# pc386ram-nobuf.net
KiCad netlist of a schematic drawn in EAGLE
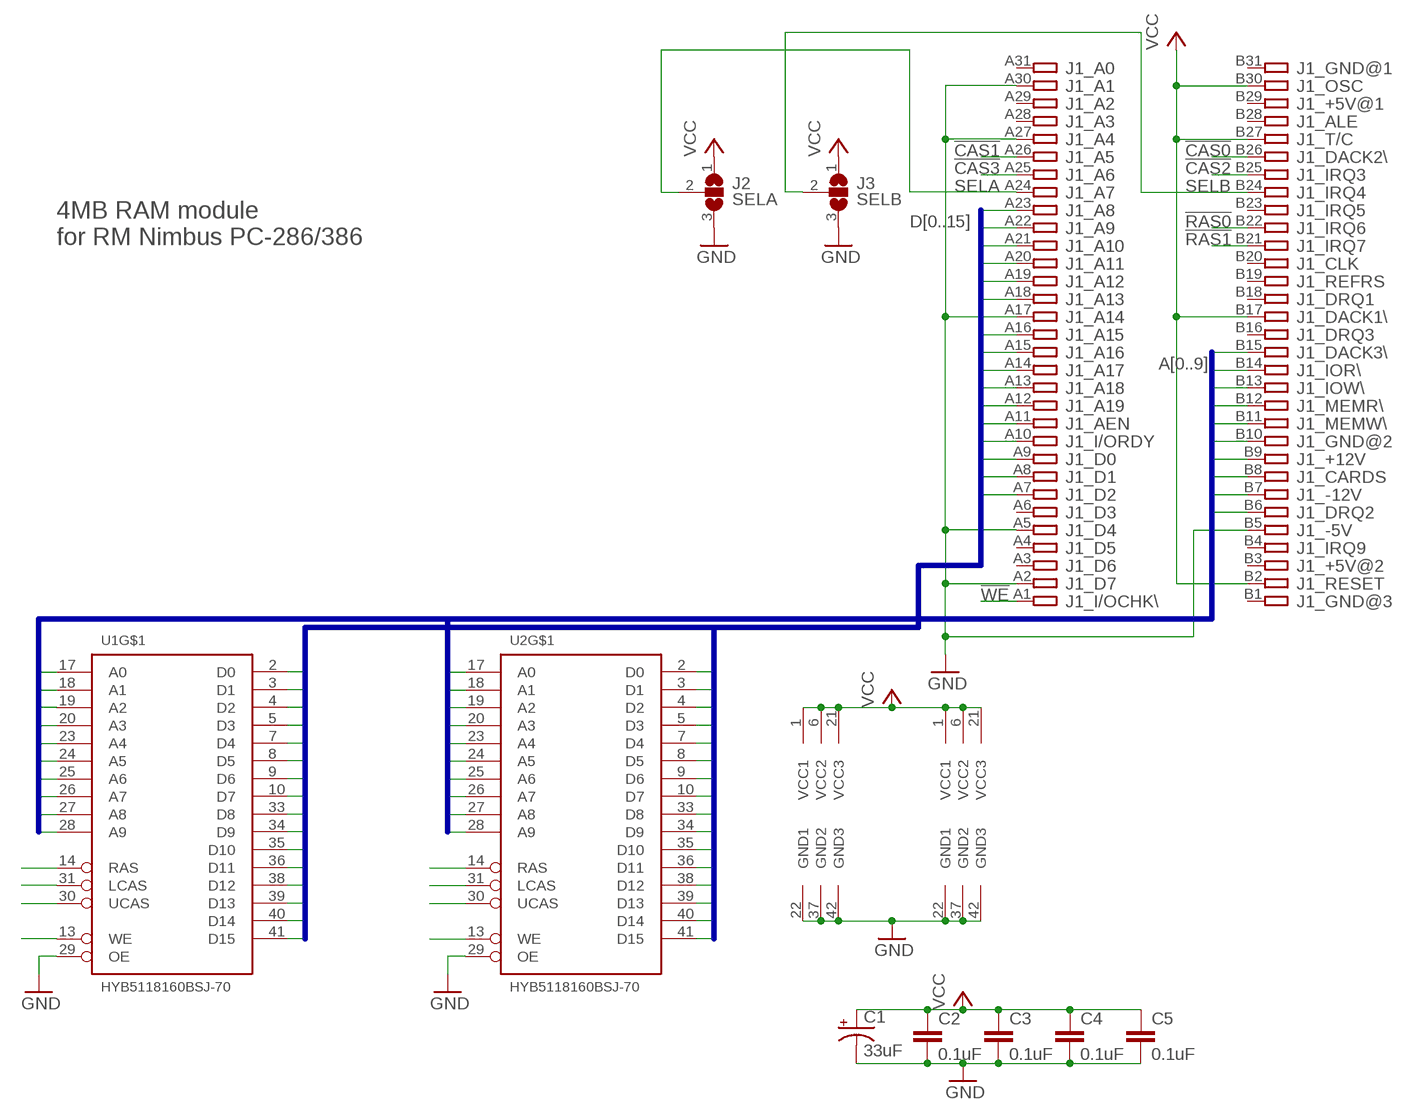
[diagram p0: schematic, sheet 1]

(export (version "E")
  (design (tool "Eeschema 10.0.6"))
  (components
    (comp (ref "C1")
      (value "33uF")
      (footprint "eagle-import:E2,5-7")
      (libsource (lib "eagle-import") (part "CPOL-USE2.5-7"))
    )
    (comp (ref "C2")
      (value "0.1uF")
      (footprint "eagle-import:C050-024X044")
      (libsource (lib "eagle-import") (part "C-EU050-024X044"))
    )
    (comp (ref "C3")
      (value "0.1uF")
      (footprint "eagle-import:C050-024X044")
      (libsource (lib "eagle-import") (part "C-EU050-024X044"))
    )
    (comp (ref "C4")
      (value "0.1uF")
      (footprint "eagle-import:C050-024X044")
      (libsource (lib "eagle-import") (part "C-EU050-024X044"))
    )
    (comp (ref "C5")
      (value "0.1uF")
      (footprint "eagle-import:C050-024X044")
      (libsource (lib "eagle-import") (part "C-EU050-024X044"))
    )
    (comp (ref "J1")
      (value "PC-386 RAM slot")
      (footprint "eagle-import:IBM8BIT")
      (libsource (lib "eagle-import") (part "IBM8BIT"))
    )
    (comp (ref "J2")
      (value "SELA")
      (footprint "eagle-import:SJ_2")
      (libsource (lib "eagle-import") (part "SJ2W"))
    )
    (comp (ref "J3")
      (value "SELB")
      (footprint "eagle-import:SJ_2")
      (libsource (lib "eagle-import") (part "SJ2W"))
    )
    (comp (ref "U1")
      (value "HYB5118160BSJ-70")
      (footprint "eagle-import:SOJ-42")
      (libsource (lib "eagle-import") (part "HYB5118160BSJ-70"))
    )
    (comp (ref "U2")
      (value "HYB5118160BSJ-70")
      (footprint "eagle-import:SOJ-42")
      (libsource (lib "eagle-import") (part "HYB5118160BSJ-70"))
    )
  )
  (nets
    (net (code "1") (name "/A0") (class "Default")
      (node (ref "J1") (pin "B6") (pinfunction "P_B6") (pintype "bidirectional"))
      (node (ref "U1") (pin "17") (pinfunction "A0_17") (pintype "input"))
      (node (ref "U2") (pin "17") (pinfunction "A0_17") (pintype "input"))
    )
    (net (code "2") (name "/A1") (class "Default")
      (node (ref "J1") (pin "B7") (pinfunction "P_B7") (pintype "bidirectional"))
      (node (ref "U1") (pin "18") (pinfunction "A1_18") (pintype "input"))
      (node (ref "U2") (pin "18") (pinfunction "A1_18") (pintype "input"))
    )
    (net (code "3") (name "/A2") (class "Default")
      (node (ref "J1") (pin "B8") (pinfunction "P_B8") (pintype "bidirectional"))
      (node (ref "U1") (pin "19") (pinfunction "A2_19") (pintype "input"))
      (node (ref "U2") (pin "19") (pinfunction "A2_19") (pintype "input"))
    )
    (net (code "4") (name "/A3") (class "Default")
      (node (ref "J1") (pin "B9") (pinfunction "P_B9") (pintype "bidirectional"))
      (node (ref "U1") (pin "20") (pinfunction "A3_20") (pintype "input"))
      (node (ref "U2") (pin "20") (pinfunction "A3_20") (pintype "input"))
    )
    (net (code "5") (name "/A4") (class "Default")
      (node (ref "J1") (pin "B10") (pinfunction "P_B10") (pintype "bidirectional"))
      (node (ref "U1") (pin "23") (pinfunction "A4_23") (pintype "input"))
      (node (ref "U2") (pin "23") (pinfunction "A4_23") (pintype "input"))
    )
    (net (code "6") (name "/A5") (class "Default")
      (node (ref "J1") (pin "B11") (pinfunction "P_B11") (pintype "bidirectional"))
      (node (ref "U1") (pin "24") (pinfunction "A5_24") (pintype "input"))
      (node (ref "U2") (pin "24") (pinfunction "A5_24") (pintype "input"))
    )
    (net (code "7") (name "/A6") (class "Default")
      (node (ref "J1") (pin "B12") (pinfunction "P_B12") (pintype "bidirectional"))
      (node (ref "U1") (pin "25") (pinfunction "A6_25") (pintype "input"))
      (node (ref "U2") (pin "25") (pinfunction "A6_25") (pintype "input"))
    )
    (net (code "8") (name "/A7") (class "Default")
      (node (ref "J1") (pin "B13") (pinfunction "P_B13") (pintype "bidirectional"))
      (node (ref "U1") (pin "26") (pinfunction "A7_26") (pintype "input"))
      (node (ref "U2") (pin "26") (pinfunction "A7_26") (pintype "input"))
    )
    (net (code "9") (name "/A8") (class "Default")
      (node (ref "J1") (pin "B14") (pinfunction "P_B14") (pintype "bidirectional"))
      (node (ref "U1") (pin "27") (pinfunction "A8_27") (pintype "input"))
      (node (ref "U2") (pin "27") (pinfunction "A8_27") (pintype "input"))
    )
    (net (code "10") (name "/A9") (class "Default")
      (node (ref "J1") (pin "B15") (pinfunction "P_B15") (pintype "bidirectional"))
      (node (ref "U1") (pin "28") (pinfunction "A9_28") (pintype "input"))
      (node (ref "U2") (pin "28") (pinfunction "A9_28") (pintype "input"))
    )
    (net (code "12") (name "/D0") (class "Default")
      (node (ref "J1") (pin "A7") (pinfunction "P_A7") (pintype "bidirectional"))
      (node (ref "U1") (pin "2") (pinfunction "D0_2") (pintype "bidirectional"))
      (node (ref "U2") (pin "2") (pinfunction "D0_2") (pintype "bidirectional"))
    )
    (net (code "13") (name "/D1") (class "Default")
      (node (ref "J1") (pin "A8") (pinfunction "P_A8") (pintype "bidirectional"))
      (node (ref "U1") (pin "3") (pinfunction "D1_3") (pintype "bidirectional"))
      (node (ref "U2") (pin "3") (pinfunction "D1_3") (pintype "bidirectional"))
    )
    (net (code "14") (name "/D2") (class "Default")
      (node (ref "J1") (pin "A9") (pinfunction "P_A9") (pintype "bidirectional"))
      (node (ref "U1") (pin "4") (pinfunction "D2_4") (pintype "bidirectional"))
      (node (ref "U2") (pin "4") (pinfunction "D2_4") (pintype "bidirectional"))
    )
    (net (code "15") (name "/D3") (class "Default")
      (node (ref "J1") (pin "A10") (pinfunction "P_A10") (pintype "bidirectional"))
      (node (ref "U1") (pin "5") (pinfunction "D3_5") (pintype "bidirectional"))
      (node (ref "U2") (pin "5") (pinfunction "D3_5") (pintype "bidirectional"))
    )
    (net (code "16") (name "/D4") (class "Default")
      (node (ref "J1") (pin "A11") (pinfunction "P_A11") (pintype "bidirectional"))
      (node (ref "U1") (pin "7") (pinfunction "D4_7") (pintype "bidirectional"))
      (node (ref "U2") (pin "7") (pinfunction "D4_7") (pintype "bidirectional"))
    )
    (net (code "17") (name "/D5") (class "Default")
      (node (ref "J1") (pin "A12") (pinfunction "P_A12") (pintype "bidirectional"))
      (node (ref "U1") (pin "8") (pinfunction "D5_8") (pintype "bidirectional"))
      (node (ref "U2") (pin "8") (pinfunction "D5_8") (pintype "bidirectional"))
    )
    (net (code "18") (name "/D6") (class "Default")
      (node (ref "J1") (pin "A13") (pinfunction "P_A13") (pintype "bidirectional"))
      (node (ref "U1") (pin "9") (pinfunction "D6_9") (pintype "bidirectional"))
      (node (ref "U2") (pin "9") (pinfunction "D6_9") (pintype "bidirectional"))
    )
    (net (code "19") (name "/D7") (class "Default")
      (node (ref "J1") (pin "A14") (pinfunction "P_A14") (pintype "bidirectional"))
      (node (ref "U1") (pin "10") (pinfunction "D7_10") (pintype "bidirectional"))
      (node (ref "U2") (pin "10") (pinfunction "D7_10") (pintype "bidirectional"))
    )
    (net (code "20") (name "/D8") (class "Default")
      (node (ref "J1") (pin "A15") (pinfunction "P_A15") (pintype "bidirectional"))
      (node (ref "U1") (pin "33") (pinfunction "D8_33") (pintype "bidirectional"))
      (node (ref "U2") (pin "33") (pinfunction "D8_33") (pintype "bidirectional"))
    )
    (net (code "21") (name "/D9") (class "Default")
      (node (ref "J1") (pin "A16") (pinfunction "P_A16") (pintype "bidirectional"))
      (node (ref "U1") (pin "34") (pinfunction "D9_34") (pintype "bidirectional"))
      (node (ref "U2") (pin "34") (pinfunction "D9_34") (pintype "bidirectional"))
    )
    (net (code "22") (name "/D10") (class "Default")
      (node (ref "J1") (pin "A18") (pinfunction "P_A18") (pintype "bidirectional"))
      (node (ref "U1") (pin "35") (pinfunction "D10_35") (pintype "bidirectional"))
      (node (ref "U2") (pin "35") (pinfunction "D10_35") (pintype "bidirectional"))
    )
    (net (code "23") (name "/D11") (class "Default")
      (node (ref "J1") (pin "A19") (pinfunction "P_A19") (pintype "bidirectional"))
      (node (ref "U1") (pin "36") (pinfunction "D11_36") (pintype "bidirectional"))
      (node (ref "U2") (pin "36") (pinfunction "D11_36") (pintype "bidirectional"))
    )
    (net (code "24") (name "/D12") (class "Default")
      (node (ref "J1") (pin "A20") (pinfunction "P_A20") (pintype "bidirectional"))
      (node (ref "U1") (pin "38") (pinfunction "D12_38") (pintype "bidirectional"))
      (node (ref "U2") (pin "38") (pinfunction "D12_38") (pintype "bidirectional"))
    )
    (net (code "25") (name "/D13") (class "Default")
      (node (ref "J1") (pin "A21") (pinfunction "P_A21") (pintype "bidirectional"))
      (node (ref "U1") (pin "39") (pinfunction "D13_39") (pintype "bidirectional"))
      (node (ref "U2") (pin "39") (pinfunction "D13_39") (pintype "bidirectional"))
    )
    (net (code "26") (name "/D14") (class "Default")
      (node (ref "J1") (pin "A22") (pinfunction "P_A22") (pintype "bidirectional"))
      (node (ref "U1") (pin "40") (pinfunction "D14_40") (pintype "bidirectional"))
      (node (ref "U2") (pin "40") (pinfunction "D14_40") (pintype "bidirectional"))
    )
    (net (code "27") (name "/D15") (class "Default")
      (node (ref "J1") (pin "A23") (pinfunction "P_A23") (pintype "bidirectional"))
      (node (ref "U1") (pin "41") (pinfunction "D15_41") (pintype "bidirectional"))
      (node (ref "U2") (pin "41") (pinfunction "D15_41") (pintype "bidirectional"))
    )
    (net (code "29") (name "/SELA") (class "Default")
      (node (ref "J1") (pin "A24") (pinfunction "P_A24") (pintype "bidirectional"))
      (node (ref "J2") (pin "2") (pinfunction "2_2") (pintype "passive"))
    )
    (net (code "30") (name "/SELB") (class "Default")
      (node (ref "J1") (pin "B24") (pinfunction "P_B24") (pintype "bidirectional"))
      (node (ref "J3") (pin "2") (pinfunction "2_2") (pintype "passive"))
    )
    (net (code "31") (name "/~{CAS0}") (class "Default")
      (node (ref "J1") (pin "B26") (pinfunction "P_B26") (pintype "bidirectional"))
      (node (ref "U1") (pin "30") (pinfunction "UCAS_30") (pintype "input"))
    )
    (net (code "32") (name "/~{CAS1}") (class "Default")
      (node (ref "J1") (pin "A26") (pinfunction "P_A26") (pintype "bidirectional"))
      (node (ref "U1") (pin "31") (pinfunction "LCAS_31") (pintype "input"))
    )
    (net (code "33") (name "/~{CAS2}") (class "Default")
      (node (ref "J1") (pin "B25") (pinfunction "P_B25") (pintype "bidirectional"))
      (node (ref "U2") (pin "30") (pinfunction "UCAS_30") (pintype "input"))
    )
    (net (code "34") (name "/~{CAS3}") (class "Default")
      (node (ref "J1") (pin "A25") (pinfunction "P_A25") (pintype "bidirectional"))
      (node (ref "U2") (pin "31") (pinfunction "LCAS_31") (pintype "input"))
    )
    (net (code "35") (name "/~{RAS0}") (class "Default")
      (node (ref "J1") (pin "B22") (pinfunction "P_B22") (pintype "bidirectional"))
      (node (ref "U1") (pin "14") (pinfunction "RAS_14") (pintype "input"))
    )
    (net (code "36") (name "/~{RAS1}") (class "Default")
      (node (ref "J1") (pin "B21") (pinfunction "P_B21") (pintype "bidirectional"))
      (node (ref "U2") (pin "14") (pinfunction "RAS_14") (pintype "input"))
    )
    (net (code "37") (name "/~{WE}") (class "Default")
      (node (ref "J1") (pin "A1") (pinfunction "P_A1") (pintype "bidirectional"))
      (node (ref "U1") (pin "13") (pinfunction "WE_13") (pintype "input"))
      (node (ref "U2") (pin "13") (pinfunction "WE_13") (pintype "input"))
    )
    (net (code "38") (name "GND") (class "Default")
      (node (ref "C1") (pin "-") (pinfunction "-_-") (pintype "passive"))
      (node (ref "C2") (pin "2") (pinfunction "2_2") (pintype "passive"))
      (node (ref "C3") (pin "2") (pinfunction "2_2") (pintype "passive"))
      (node (ref "C4") (pin "2") (pinfunction "2_2") (pintype "passive"))
      (node (ref "C5") (pin "2") (pinfunction "2_2") (pintype "passive"))
      (node (ref "J1") (pin "A17") (pinfunction "P_A17") (pintype "bidirectional"))
      (node (ref "J1") (pin "A2") (pinfunction "P_A2") (pintype "bidirectional"))
      (node (ref "J1") (pin "A27") (pinfunction "P_A27") (pintype "bidirectional"))
      (node (ref "J1") (pin "A30") (pinfunction "P_A30") (pintype "bidirectional"))
      (node (ref "J1") (pin "A5") (pinfunction "P_A5") (pintype "bidirectional"))
      (node (ref "J1") (pin "B5") (pinfunction "P_B5") (pintype "bidirectional"))
      (node (ref "J2") (pin "3") (pinfunction "3_3") (pintype "passive"))
      (node (ref "J3") (pin "3") (pinfunction "3_3") (pintype "passive"))
      (node (ref "U1") (pin "22") (pinfunction "GND1_22") (pintype "power_in"))
      (node (ref "U1") (pin "29") (pinfunction "OE_29") (pintype "input"))
      (node (ref "U1") (pin "37") (pinfunction "GND2_37") (pintype "power_in"))
      (node (ref "U1") (pin "42") (pinfunction "GND3_42") (pintype "power_in"))
      (node (ref "U2") (pin "22") (pinfunction "GND1_22") (pintype "power_in"))
      (node (ref "U2") (pin "29") (pinfunction "OE_29") (pintype "input"))
      (node (ref "U2") (pin "37") (pinfunction "GND2_37") (pintype "power_in"))
      (node (ref "U2") (pin "42") (pinfunction "GND3_42") (pintype "power_in"))
    )
    (net (code "39") (name "VCC") (class "Default")
      (node (ref "C1") (pin "+") (pinfunction "+_+") (pintype "passive"))
      (node (ref "C2") (pin "1") (pinfunction "1_1") (pintype "passive"))
      (node (ref "C3") (pin "1") (pinfunction "1_1") (pintype "passive"))
      (node (ref "C4") (pin "1") (pinfunction "1_1") (pintype "passive"))
      (node (ref "C5") (pin "1") (pinfunction "1_1") (pintype "passive"))
      (node (ref "J1") (pin "B17") (pinfunction "P_B17") (pintype "bidirectional"))
      (node (ref "J1") (pin "B2") (pinfunction "P_B2") (pintype "bidirectional"))
      (node (ref "J1") (pin "B27") (pinfunction "P_B27") (pintype "bidirectional"))
      (node (ref "J1") (pin "B30") (pinfunction "P_B30") (pintype "bidirectional"))
      (node (ref "J2") (pin "1") (pinfunction "1_1") (pintype "passive"))
      (node (ref "J3") (pin "1") (pinfunction "1_1") (pintype "passive"))
      (node (ref "U1") (pin "1") (pinfunction "VCC1_1") (pintype "power_in"))
      (node (ref "U1") (pin "21") (pinfunction "VCC3_21") (pintype "power_in"))
      (node (ref "U1") (pin "6") (pinfunction "VCC2_6") (pintype "power_in"))
      (node (ref "U2") (pin "1") (pinfunction "VCC1_1") (pintype "power_in"))
      (node (ref "U2") (pin "21") (pinfunction "VCC3_21") (pintype "power_in"))
      (node (ref "U2") (pin "6") (pinfunction "VCC2_6") (pintype "power_in"))
    )
    (net (code "40") (name "unconnected-(J1AA-P-PadB28)") (class "Default")
      (node (ref "J1") (pin "B28") (pinfunction "P_B28") (pintype "bidirectional"))
    )
    (net (code "41") (name "unconnected-(J1AC-P-PadB20)") (class "Default")
      (node (ref "J1") (pin "B20") (pinfunction "P_B20") (pintype "bidirectional"))
    )
    (net (code "42") (name "unconnected-(J1AG-P-PadA6)") (class "Default")
      (node (ref "J1") (pin "A6") (pinfunction "P_A6") (pintype "bidirectional"))
    )
    (net (code "43") (name "unconnected-(J1AI-P-PadA4)") (class "Default")
      (node (ref "J1") (pin "A4") (pinfunction "P_A4") (pintype "bidirectional"))
    )
    (net (code "44") (name "unconnected-(J1AJ-P-PadA3)") (class "Default")
      (node (ref "J1") (pin "A3") (pinfunction "P_A3") (pintype "bidirectional"))
    )
    (net (code "45") (name "unconnected-(J1AO-P-PadB18)") (class "Default")
      (node (ref "J1") (pin "B18") (pinfunction "P_B18") (pintype "bidirectional"))
    )
    (net (code "46") (name "unconnected-(J1AQ-P-PadB16)") (class "Default")
      (node (ref "J1") (pin "B16") (pinfunction "P_B16") (pintype "bidirectional"))
    )
    (net (code "47") (name "unconnected-(J1AR-P-PadB31)") (class "Default")
      (node (ref "J1") (pin "B31") (pinfunction "P_B31") (pintype "bidirectional"))
    )
    (net (code "48") (name "unconnected-(J1AT-P-PadB1)") (class "Default")
      (node (ref "J1") (pin "B1") (pinfunction "P_B1") (pintype "bidirectional"))
    )
    (net (code "49") (name "unconnected-(J1B-P-PadB29)") (class "Default")
      (node (ref "J1") (pin "B29") (pinfunction "P_B29") (pintype "bidirectional"))
    )
    (net (code "50") (name "unconnected-(J1BA-P-PadB23)") (class "Default")
      (node (ref "J1") (pin "B23") (pinfunction "P_B23") (pintype "bidirectional"))
    )
    (net (code "51") (name "unconnected-(J1BD-P-PadB4)") (class "Default")
      (node (ref "J1") (pin "B4") (pinfunction "P_B4") (pintype "bidirectional"))
    )
    (net (code "52") (name "unconnected-(J1BH-P-PadB19)") (class "Default")
      (node (ref "J1") (pin "B19") (pinfunction "P_B19") (pintype "bidirectional"))
    )
    (net (code "53") (name "unconnected-(J1C-P-PadB3)") (class "Default")
      (node (ref "J1") (pin "B3") (pinfunction "P_B3") (pintype "bidirectional"))
    )
    (net (code "54") (name "unconnected-(J1F-P-PadA31)") (class "Default")
      (node (ref "J1") (pin "A31") (pinfunction "P_A31") (pintype "bidirectional"))
    )
    (net (code "55") (name "unconnected-(J1R-P-PadA29)") (class "Default")
      (node (ref "J1") (pin "A29") (pinfunction "P_A29") (pintype "bidirectional"))
    )
    (net (code "56") (name "unconnected-(J1S-P-PadA28)") (class "Default")
      (node (ref "J1") (pin "A28") (pinfunction "P_A28") (pintype "bidirectional"))
    )
  )
)
